# design.net
KiCad netlist of a schematic drawn in Altium Designer
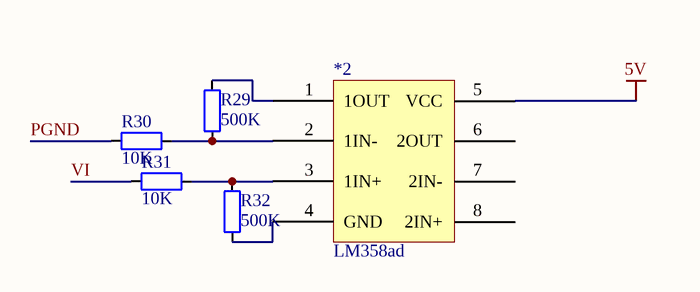
[diagram p0: 放大电路.SchDoc]

(export (version "E")
  (design (tool "Eeschema 10.0.6"))
  (components
    (comp (ref "*2") (value "LM358ad") (footprint "SOP_E150_8") (libsource (lib "LM358AD") (part "LM358ad")))
    (comp (ref "R29")
      (value "500K")
      (footprint "RES_0603")
      (description "Resistor")
      (fields (field (name "Comment") "Res_0603"))
      (libsource (lib "Integrated_Library") (part "Res_0603"))
    )
    (comp (ref "R30")
      (value "10K")
      (footprint "RES_0603")
      (description "Resistor")
      (fields (field (name "Comment") "Res_0603"))
      (libsource (lib "") (part "Res_0603_1"))
    )
    (comp (ref "R31")
      (value "10K")
      (footprint "RES_0603")
      (description "Resistor")
      (fields (field (name "Comment") "Res_0603"))
      (libsource (lib "") (part "Res_0603_1"))
    )
    (comp (ref "R32")
      (value "500K")
      (footprint "RES_0603")
      (description "Resistor")
      (fields (field (name "Comment") "Res_0603"))
      (libsource (lib "Integrated_Library") (part "Res_0603"))
    )
  )
  (nets
    (net (code "1") (name "/PGND") (class "Default")
      (node (ref "R30") (pin "1") (pinfunction "1_1") (pintype "passive"))
    )
    (net (code "2") (name "/VI") (class "Default")
      (node (ref "R31") (pin "1") (pinfunction "1_1") (pintype "passive"))
    )
    (net (code "3") (name "5V") (class "Default")
      (node (ref "*2") (pin "5") (pinfunction "VCC_5") (pintype "passive"))
    )
    (net (code "4") (name "Net-(*2-1IN+)") (class "Default")
      (node (ref "*2") (pin "3") (pinfunction "1IN+_3") (pintype "passive"))
      (node (ref "R31") (pin "2") (pinfunction "2_2") (pintype "passive"))
      (node (ref "R32") (pin "2") (pinfunction "2_2") (pintype "passive"))
    )
    (net (code "5") (name "Net-(*2-1IN-)") (class "Default")
      (node (ref "*2") (pin "2") (pinfunction "1IN-_2") (pintype "passive"))
      (node (ref "R29") (pin "1") (pinfunction "1_1") (pintype "passive"))
      (node (ref "R30") (pin "2") (pinfunction "2_2") (pintype "passive"))
    )
    (net (code "6") (name "Net-(*2-1OUT)") (class "Default")
      (node (ref "*2") (pin "1") (pinfunction "1OUT_1") (pintype "passive"))
      (node (ref "R29") (pin "2") (pinfunction "2_2") (pintype "passive"))
    )
    (net (code "7") (name "Net-(*2-GND)") (class "Default")
      (node (ref "*2") (pin "4") (pinfunction "GND_4") (pintype "passive"))
      (node (ref "R32") (pin "1") (pinfunction "1_1") (pintype "passive"))
    )
    (net (code "8") (name "unconnected-(*2-2IN+-Pad8)") (class "Default")
      (node (ref "*2") (pin "8") (pinfunction "2IN+_8") (pintype "passive"))
    )
    (net (code "9") (name "unconnected-(*2-2IN--Pad7)") (class "Default")
      (node (ref "*2") (pin "7") (pinfunction "2IN-_7") (pintype "passive"))
    )
    (net (code "10") (name "unconnected-(*2-2OUT-Pad6)") (class "Default")
      (node (ref "*2") (pin "6") (pinfunction "2OUT_6") (pintype "passive"))
    )
  )
)
